# Uni-2_0_Complete.net
KiCad netlist of a schematic drawn in EAGLE
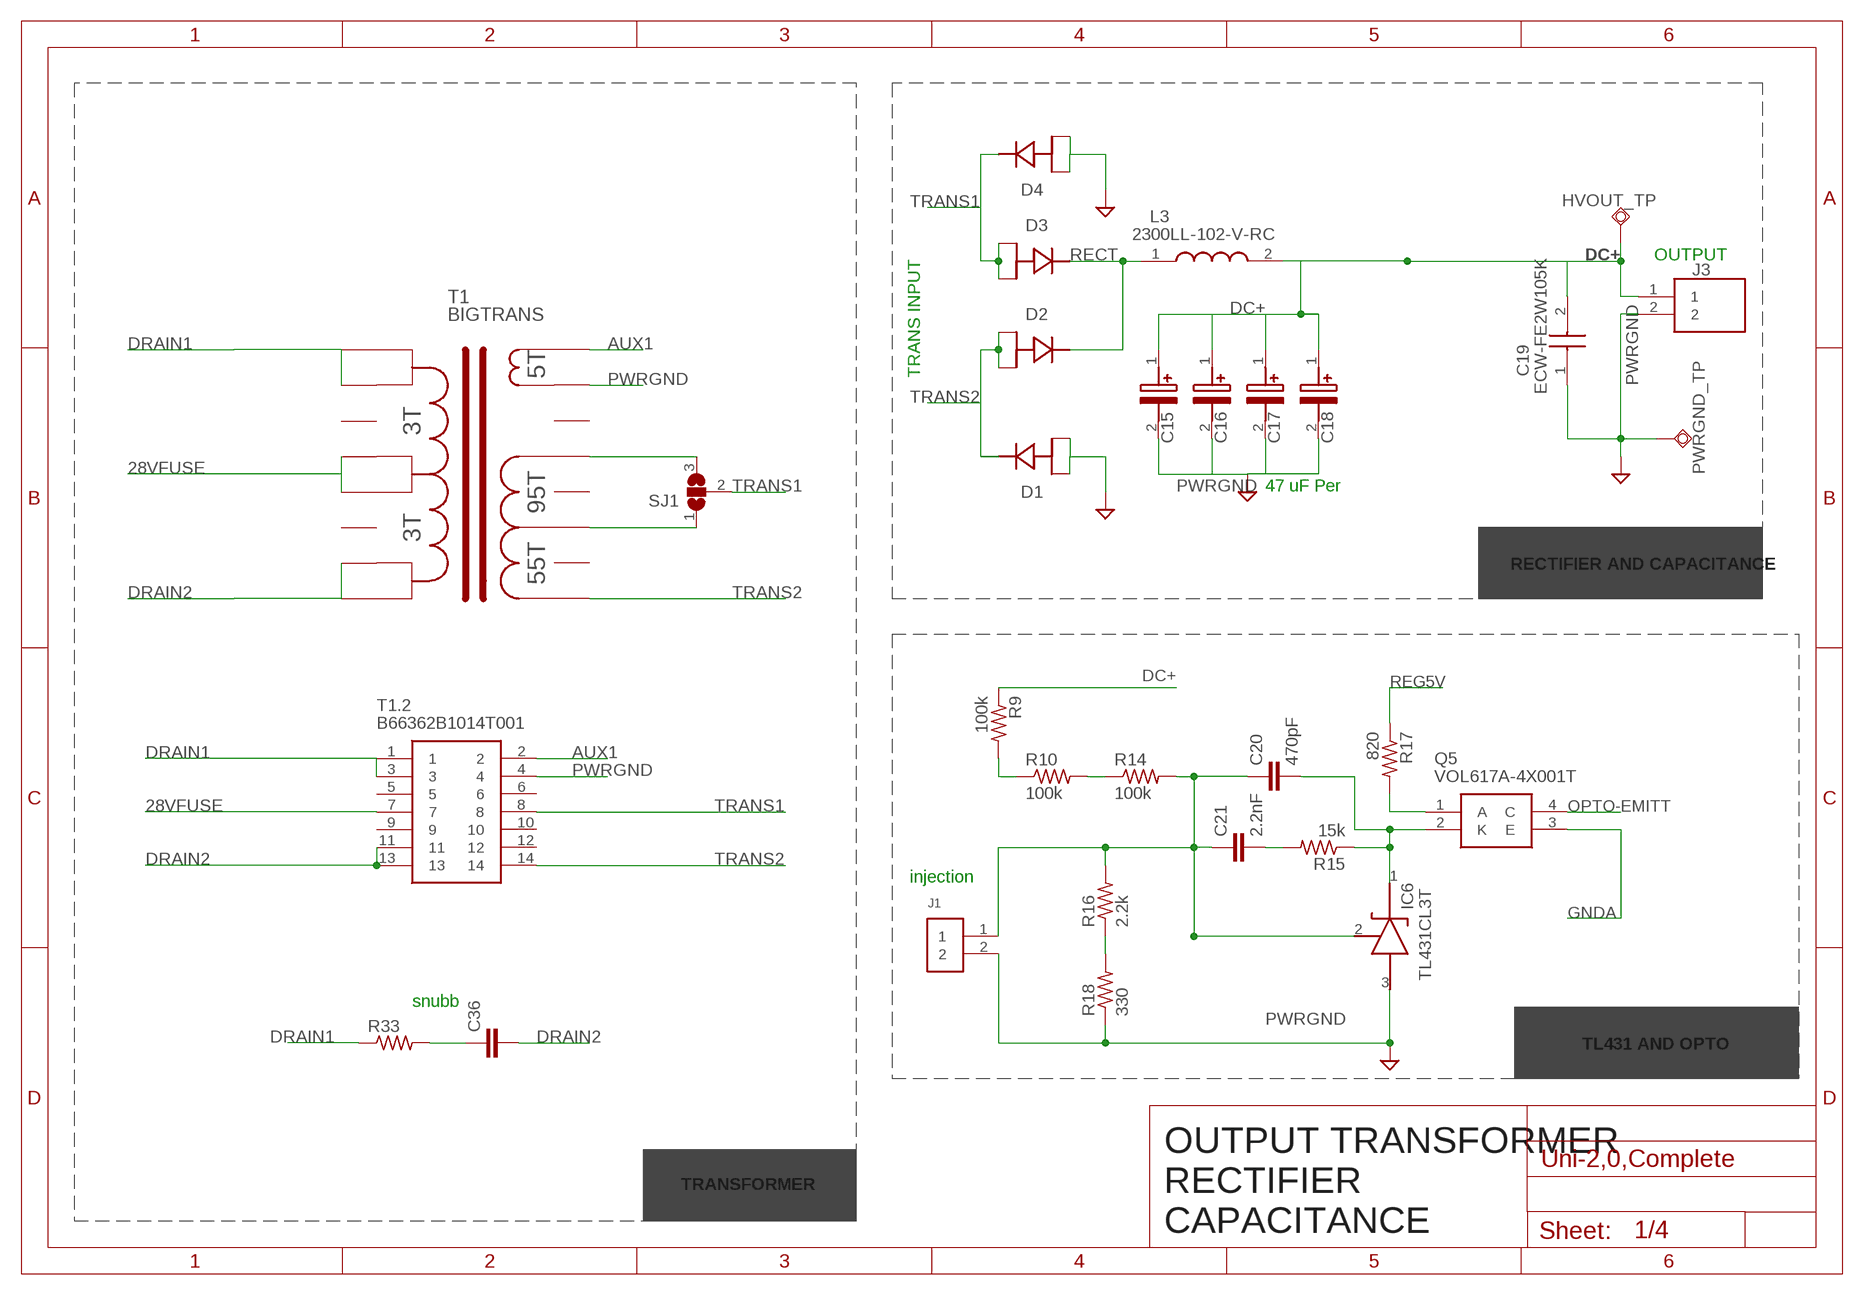
[diagram p0: schematic, sheet 1]
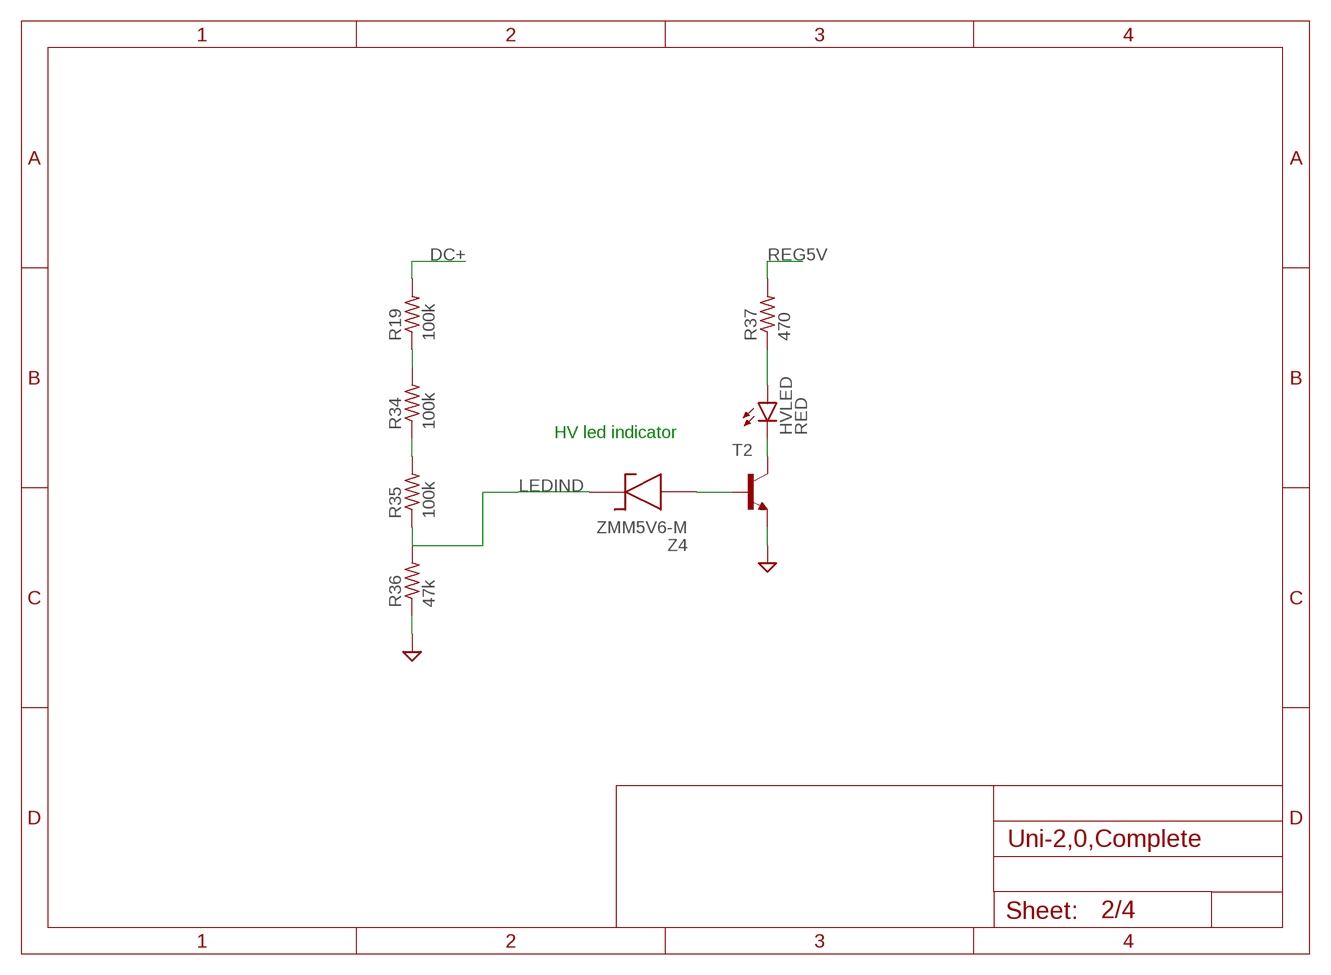
[diagram p1: schematic, sheet 2]
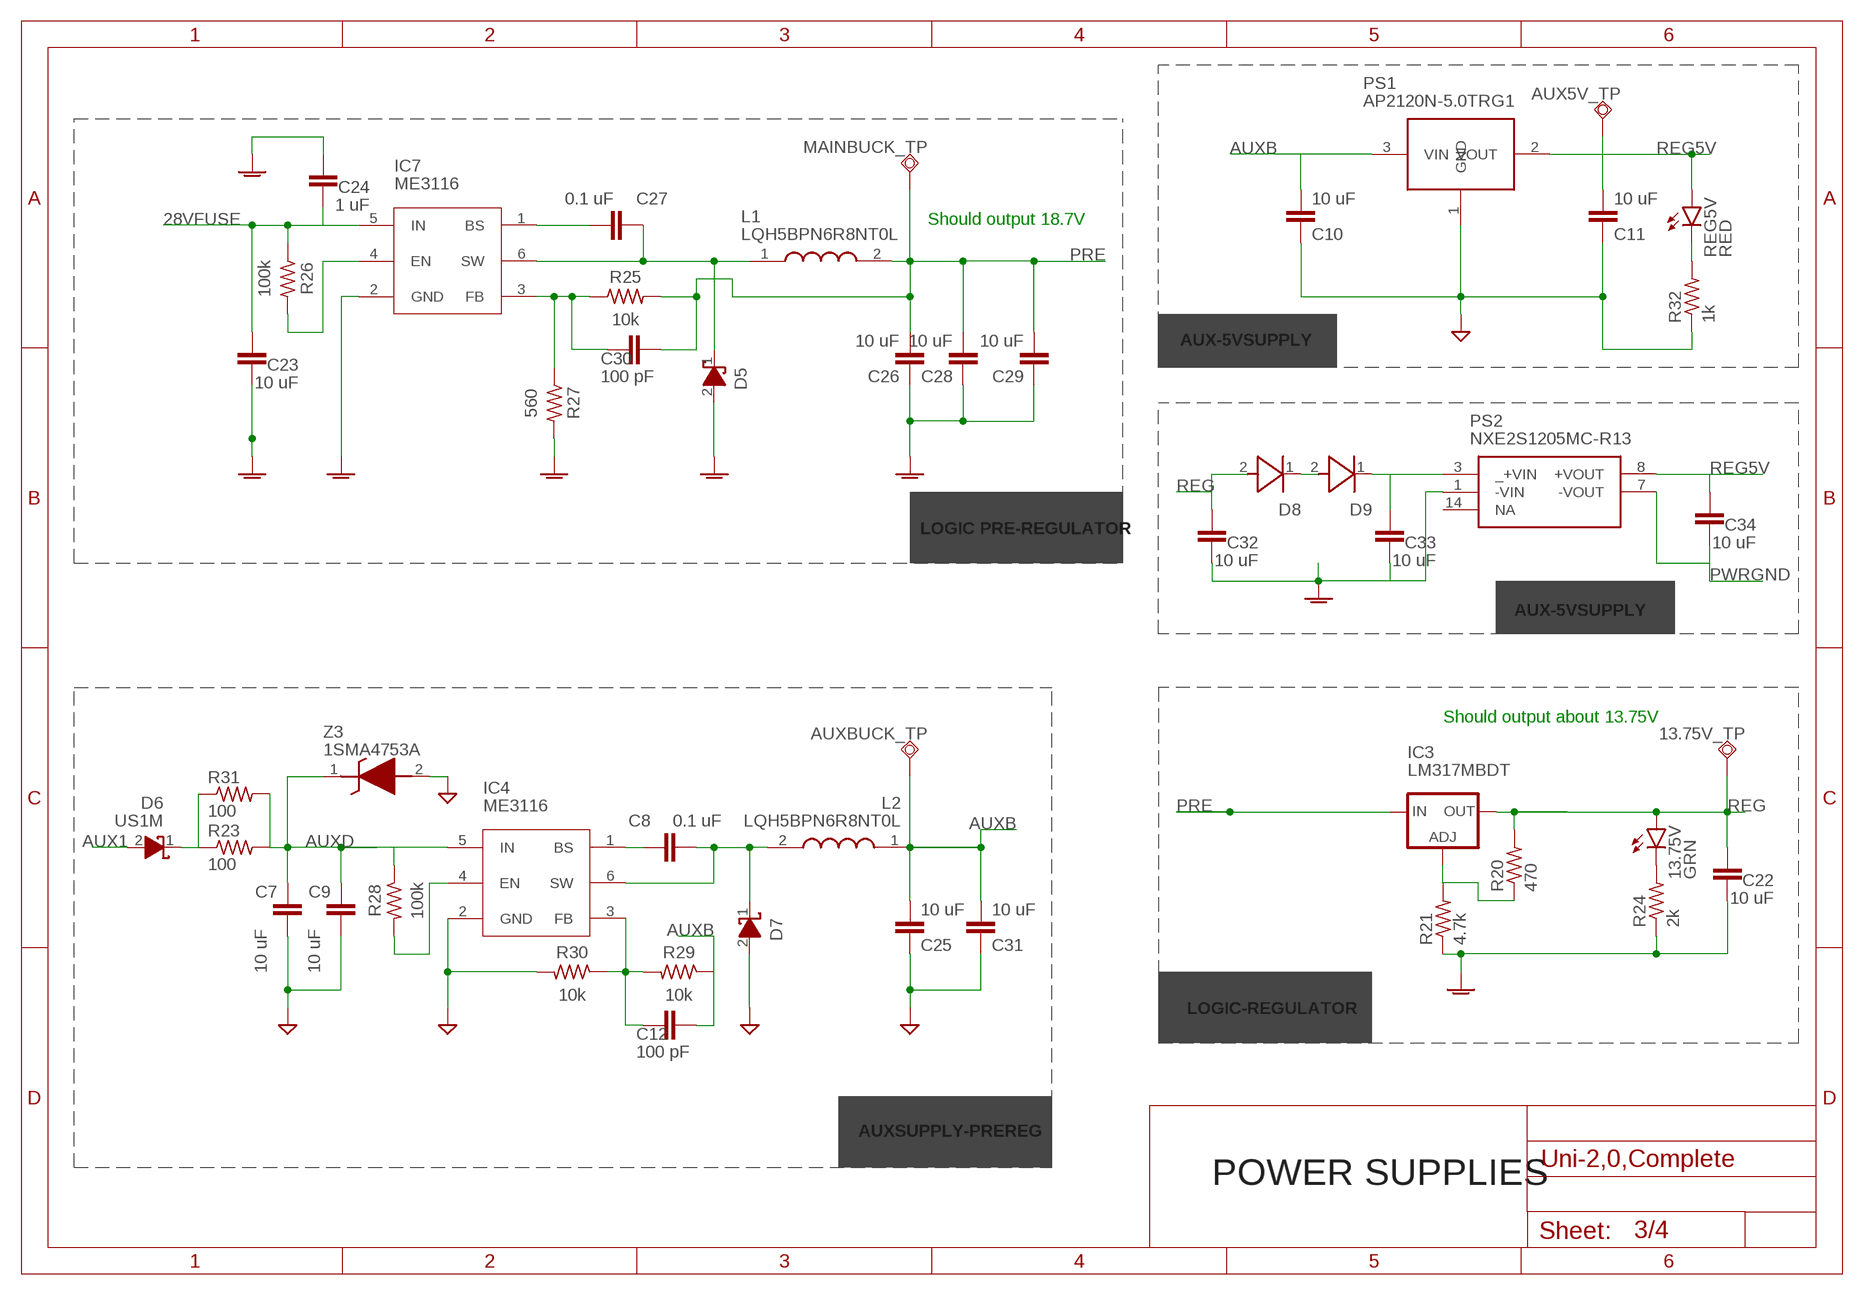
[diagram p2: schematic, sheet 3]
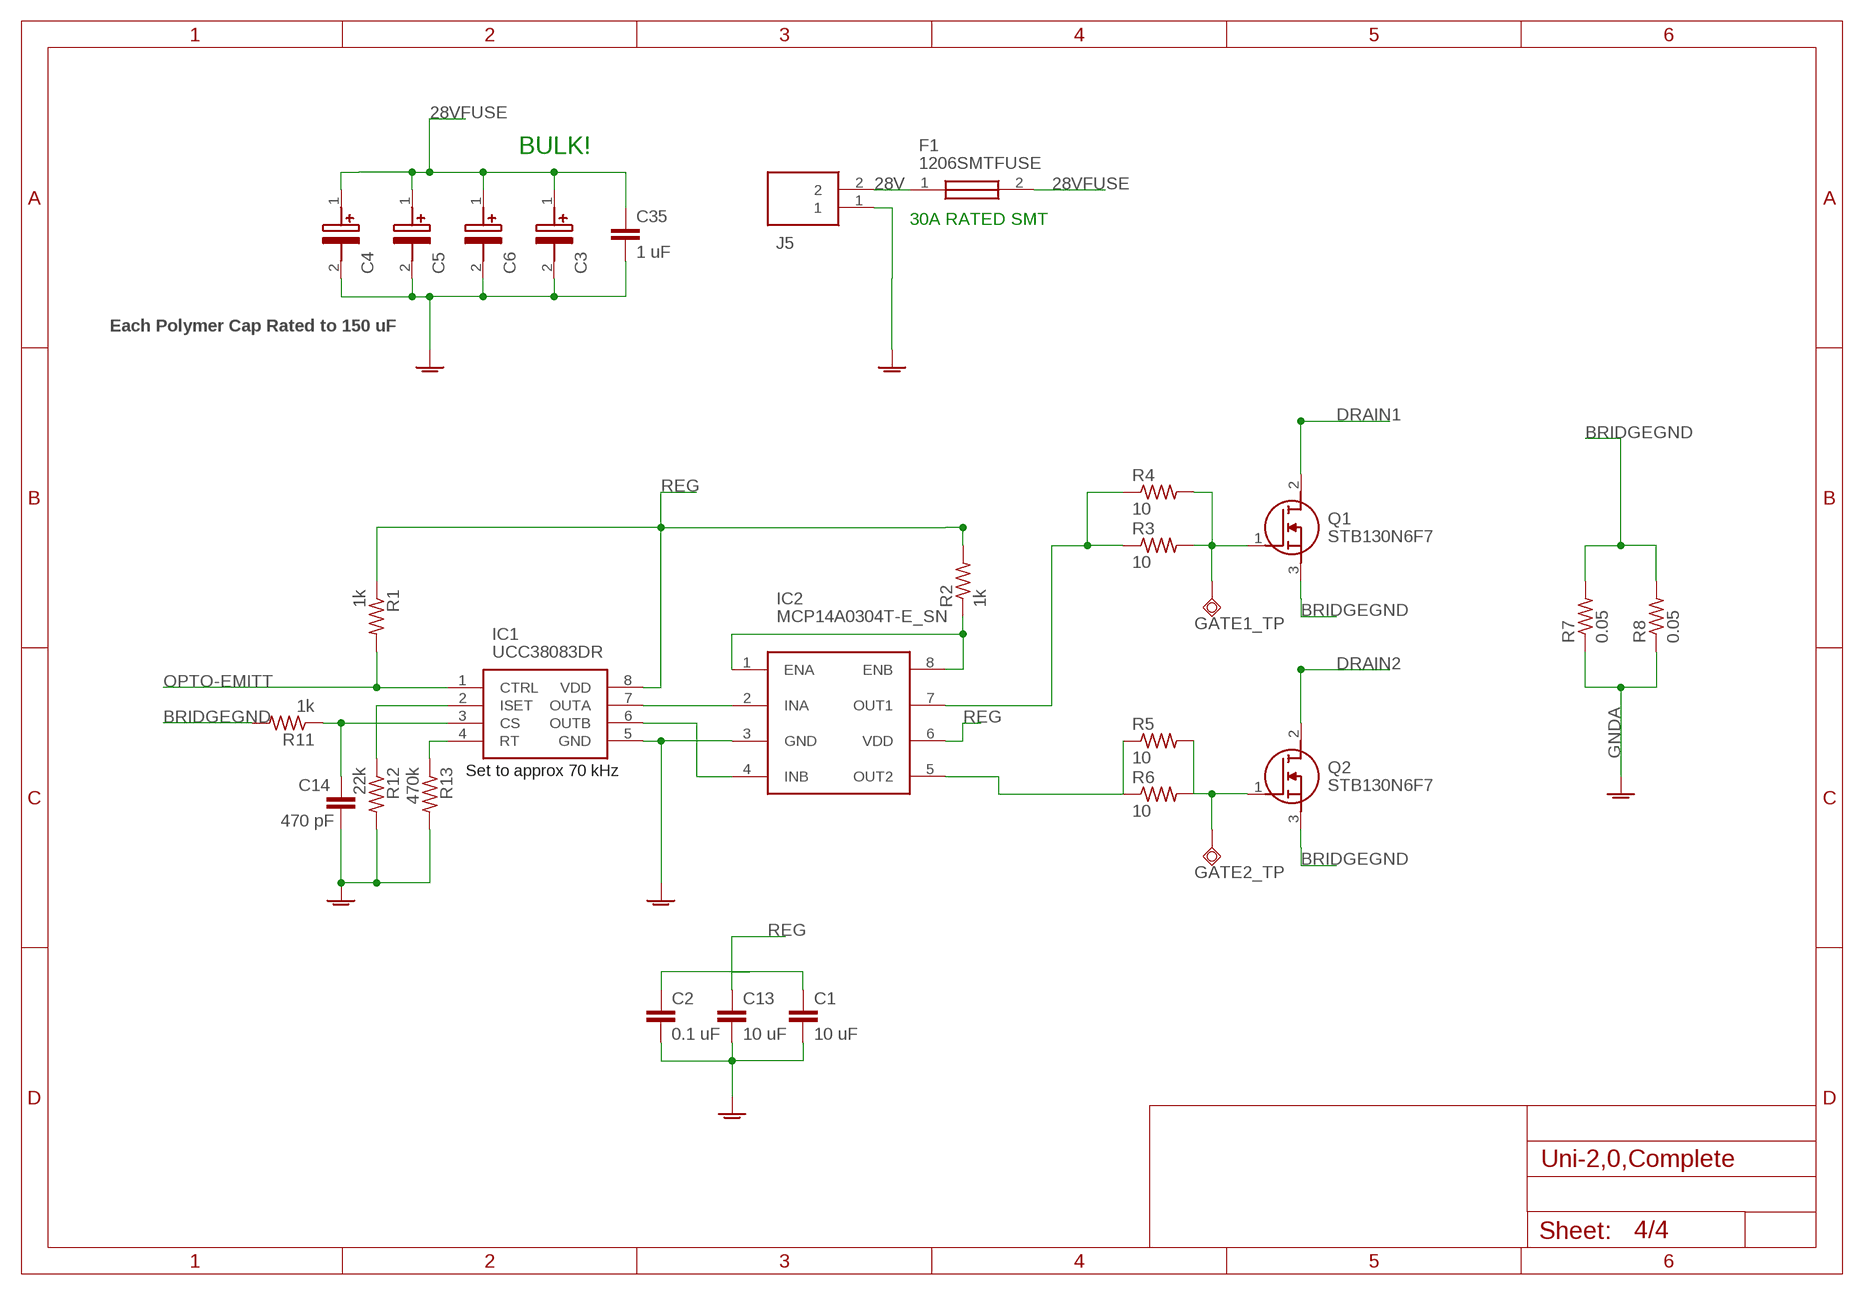
[diagram p3: schematic, sheet 4]

(export (version "E")
  (design (tool "Eeschema 10.0.6"))
  (components
    (comp (ref "C15")
      (value "EEU-ED2V470S")
      (footprint "eagle-import:CAPPRD750W85D1800H2200")
      (fields (field (name "MOUSER_PART_NUMBER") "667-EEU-ED2V470S"))
      (libsource (lib "eagle-import") (part "EEU-ED2V470S"))
    )
    (comp (ref "C16")
      (value "EEU-ED2V470S")
      (footprint "eagle-import:CAPPRD750W85D1800H2200")
      (fields (field (name "MOUSER_PART_NUMBER") "667-EEU-ED2V470S"))
      (libsource (lib "eagle-import") (part "EEU-ED2V470S"))
    )
    (comp (ref "C17")
      (value "EEU-ED2V470S")
      (footprint "eagle-import:CAPPRD750W85D1800H2200")
      (fields (field (name "MOUSER_PART_NUMBER") "667-EEU-ED2V470S"))
      (libsource (lib "eagle-import") (part "EEU-ED2V470S"))
    )
    (comp (ref "C18")
      (value "EEU-ED2V470S")
      (footprint "eagle-import:CAPPRD750W85D1800H2200")
      (fields (field (name "MOUSER_PART_NUMBER") "667-EEU-ED2V470S"))
      (libsource (lib "eagle-import") (part "EEU-ED2V470S"))
    )
    (comp (ref "C19")
      (value "ECW-FE2W105K")
      (footprint "eagle-import:ECWFE2W105K")
      (libsource (lib "eagle-import") (part "ECW-FE2W105K"))
    )
    (comp (ref "C20")
      (value "470pF")
      (footprint "eagle-import:C0603K")
      (libsource (lib "eagle-import") (part "rcl_334_C-EUC0603K"))
    )
    (comp (ref "C21")
      (value "2.2nF")
      (footprint "eagle-import:C0603K")
      (libsource (lib "eagle-import") (part "rcl_334_C-EUC0603K"))
    )
    (comp (ref "C36")
      (value "C-EUC1210K")
      (footprint "eagle-import:C1210K")
      (libsource (lib "eagle-import") (part "rcl_334_C-EUC1210K"))
    )
    (comp (ref "D1")
      (value "FERD20H60CG-TR")
      (footprint "eagle-import:STB20N95K5")
      (fields (field (name "MOUSER_PART_NUMBER") "511-FERD20H60CG-TR"))
      (libsource (lib "eagle-import") (part "FERD20H60CG-TR"))
    )
    (comp (ref "D2")
      (value "FERD20H60CG-TR")
      (footprint "eagle-import:STB20N95K5")
      (fields (field (name "MOUSER_PART_NUMBER") "511-FERD20H60CG-TR"))
      (libsource (lib "eagle-import") (part "FERD20H60CG-TR"))
    )
    (comp (ref "D3")
      (value "FERD20H60CG-TR")
      (footprint "eagle-import:STB20N95K5")
      (fields (field (name "MOUSER_PART_NUMBER") "511-FERD20H60CG-TR"))
      (libsource (lib "eagle-import") (part "FERD20H60CG-TR"))
    )
    (comp (ref "D4")
      (value "FERD20H60CG-TR")
      (footprint "eagle-import:STB20N95K5")
      (fields (field (name "MOUSER_PART_NUMBER") "511-FERD20H60CG-TR"))
      (libsource (lib "eagle-import") (part "FERD20H60CG-TR"))
    )
    (comp (ref "HVOUT_TP")
      (value "TPSQPAD1-13")
      (footprint "eagle-import:P1-13")
      (libsource (lib "eagle-import") (part "TPSQPAD1-13"))
    )
    (comp (ref "IC6")
      (value "TL431CL3T")
      (footprint "eagle-import:SOT95P237X112-3N")
      (fields (field (name "MOUSER_PART_NUMBER") "511-TL431CL3T"))
      (libsource (lib "eagle-import") (part "TL431CL3T"))
    )
    (comp (ref "J1")
      (value "61300211121")
      (footprint "eagle-import:61300211121")
      (fields
        (field (name "DIGI_KEY_PART_NUMBER") "732-5315-ND")
        (field (name "MANUFACTURER") "Wurth Electronics Inc.")
        (field (name "CREATED_BY") "PCBLayout.com")
      )
      (libsource (lib "eagle-import") (part "61300211121"))
    )
    (comp (ref "J3")
      (value "2305908-2")
      (footprint "eagle-import:23059082")
      (fields (field (name "MOUSER_PART_NUMBER") "571-2305908-2"))
      (libsource (lib "eagle-import") (part "2305908-2"))
    )
    (comp (ref "L3")
      (value "2300LL-102-V-RC")
      (footprint "eagle-import:2300LL102VRC")
      (fields (field (name "MOUSER_PART_NUMBER") "652-2300LL-102-V-RC"))
      (libsource (lib "eagle-import") (part "2300LL-102-V-RC"))
    )
    (comp (ref "PWRGND_TP")
      (value "TPSQPAD1-13")
      (footprint "eagle-import:P1-13")
      (libsource (lib "eagle-import") (part "TPSQPAD1-13"))
    )
    (comp (ref "Q5")
      (value "VOL617A-4X001T")
      (footprint "eagle-import:SOP254P1015X230-4N")
      (fields (field (name "MOUSER_PART_NUMBER") "78-VOL617A-4X001T"))
      (libsource (lib "eagle-import") (part "VOL617A-4X001T"))
    )
    (comp (ref "R9")
      (value "100k")
      (footprint "eagle-import:R1206")
      (libsource (lib "eagle-import") (part "R-US_R1206"))
    )
    (comp (ref "R10")
      (value "100k")
      (footprint "eagle-import:R1206")
      (libsource (lib "eagle-import") (part "R-US_R1206"))
    )
    (comp (ref "R14")
      (value "100k")
      (footprint "eagle-import:R1206")
      (libsource (lib "eagle-import") (part "R-US_R1206"))
    )
    (comp (ref "R15")
      (value "15k")
      (footprint "eagle-import:R0603")
      (libsource (lib "eagle-import") (part "R-US_R0603"))
    )
    (comp (ref "R16")
      (value "2.2k")
      (footprint "eagle-import:R0805")
      (libsource (lib "eagle-import") (part "R-US_R0805"))
    )
    (comp (ref "R17")
      (value "820")
      (footprint "eagle-import:R0603")
      (libsource (lib "eagle-import") (part "R-US_R0603"))
    )
    (comp (ref "R18")
      (value "330")
      (footprint "eagle-import:R0805")
      (libsource (lib "eagle-import") (part "R-US_R0805"))
    )
    (comp (ref "R33")
      (value "R-US_R1206")
      (footprint "eagle-import:R1206")
      (libsource (lib "eagle-import") (part "R-US_R1206"))
    )
    (comp (ref "SJ1")
      (value "SJ2WW")
      (footprint "eagle-import:SJ_2W")
      (libsource (lib "eagle-import") (part "SJ2WW"))
    )
    (comp (ref "T1")
      (value "BIGTRANS")
      (footprint "eagle-import:BIGTRANS!")
      (libsource (lib "eagle-import") (part "BIGTRANS"))
    )
    (comp (ref "T1.2")
      (value "B66362B1014T001")
      (footprint "eagle-import:B66362B1014T001")
      (fields (field (name "MOUSER_PART_NUMBER") "871-B66362B1014T001"))
      (libsource (lib "eagle-import") (part "B66362B1014T001"))
    )
    (comp (ref "C1")
      (value "10 uF")
      (footprint "eagle-import:C0603K")
      (fields (field (name "LCSC_PART") "C440198"))
      (libsource (lib "eagle-import") (part "rcl_334_C-EUC0603K"))
    )
    (comp (ref "C2")
      (value "0.1 uF")
      (footprint "eagle-import:C0603K")
      (fields (field (name "LCSC_PART") "C440198"))
      (libsource (lib "eagle-import") (part "rcl_334_C-EUC0603K"))
    )
    (comp (ref "C3")
      (value "OVK151M1VTR-10131")
      (footprint "eagle-import:16SVF1000M")
      (libsource (lib "eagle-import") (part "OVK151M1VTR-10131"))
    )
    (comp (ref "C4")
      (value "OVK151M1VTR-10131")
      (footprint "eagle-import:16SVF1000M")
      (libsource (lib "eagle-import") (part "OVK151M1VTR-10131"))
    )
    (comp (ref "C5")
      (value "OVK151M1VTR-10131")
      (footprint "eagle-import:16SVF1000M")
      (libsource (lib "eagle-import") (part "OVK151M1VTR-10131"))
    )
    (comp (ref "C6")
      (value "OVK151M1VTR-10131")
      (footprint "eagle-import:16SVF1000M")
      (libsource (lib "eagle-import") (part "OVK151M1VTR-10131"))
    )
    (comp (ref "C13")
      (value "10 uF")
      (footprint "eagle-import:C0603K")
      (fields (field (name "LCSC_PART") "C440198"))
      (libsource (lib "eagle-import") (part "rcl_334_C-EUC0603K"))
    )
    (comp (ref "C14")
      (value "470 pF")
      (footprint "eagle-import:C0603K")
      (fields (field (name "LCSC_PART") "C1620"))
      (libsource (lib "eagle-import") (part "rcl_334_C-EUC0603K"))
    )
    (comp (ref "C35")
      (value "1 uF")
      (footprint "eagle-import:C0805K")
      (fields (field (name "LCSC_PART") "C440198"))
      (libsource (lib "eagle-import") (part "rcl_334_C-EUC0805K"))
    )
    (comp (ref "F1")
      (value "1206SMTFUSE")
      (footprint "eagle-import:1206SMTFUSE")
      (fields
        (field (name "MANUFACTURER_PART_NUMBER") "0685P9400-01")
        (field (name "MOUSER_PART_NUMBER") "530-0685P9400-01")
      )
      (libsource (lib "eagle-import") (part "1206SMTFUSE"))
    )
    (comp (ref "GATE1_TP")
      (value "TPSQPAD1-17")
      (footprint "eagle-import:P1-17")
      (libsource (lib "eagle-import") (part "TPSQPAD1-17"))
    )
    (comp (ref "GATE2_TP")
      (value "TPSQPAD1-17")
      (footprint "eagle-import:P1-17")
      (libsource (lib "eagle-import") (part "TPSQPAD1-17"))
    )
    (comp (ref "IC1")
      (value "UCC38083DR")
      (footprint "eagle-import:SOIC127P600X175-8N")
      (fields (field (name "MOUSER_PART_NUMBER") "595-UCC38083DR"))
      (libsource (lib "eagle-import") (part "UCC38083DR"))
    )
    (comp (ref "IC2")
      (value "MCP14A0304T-E_SN")
      (footprint "eagle-import:SOIC127P600X175-8N")
      (fields
        (field (name "MANUFACTURER_PART_NUMBER") "MCP14A0304T-E/SN")
        (field (name "MOUSER_PART_NUMBER") "579-MCP14A0304T-E/SN")
      )
      (libsource (lib "eagle-import") (part "MCP14A0304T-E_SN"))
    )
    (comp (ref "J5")
      (value "2305908-2")
      (footprint "eagle-import:23059082")
      (fields (field (name "MOUSER_PART_NUMBER") "571-2305908-2"))
      (libsource (lib "eagle-import") (part "2305908-2"))
    )
    (comp (ref "Q1")
      (value "STB130N6F7")
      (footprint "eagle-import:D2PAK")
      (libsource (lib "eagle-import") (part "STB130N6F7"))
    )
    (comp (ref "Q2")
      (value "STB130N6F7")
      (footprint "eagle-import:D2PAK")
      (libsource (lib "eagle-import") (part "STB130N6F7"))
    )
    (comp (ref "R1")
      (value "1k")
      (footprint "eagle-import:R0603")
      (fields (field (name "LCSC_PART") "C22975"))
      (libsource (lib "eagle-import") (part "R-US_R0603"))
    )
    (comp (ref "R2")
      (value "1k")
      (footprint "eagle-import:R0402")
      (libsource (lib "eagle-import") (part "R-US_R0402"))
    )
    (comp (ref "R3")
      (value "10")
      (footprint "eagle-import:R0805")
      (libsource (lib "eagle-import") (part "R-US_R0805"))
    )
    (comp (ref "R4")
      (value "10")
      (footprint "eagle-import:R0805")
      (libsource (lib "eagle-import") (part "R-US_R0805"))
    )
    (comp (ref "R5")
      (value "10")
      (footprint "eagle-import:R0805")
      (libsource (lib "eagle-import") (part "R-US_R0805"))
    )
    (comp (ref "R6")
      (value "10")
      (footprint "eagle-import:R0805")
      (libsource (lib "eagle-import") (part "R-US_R0805"))
    )
    (comp (ref "R7")
      (value "0.05")
      (footprint "eagle-import:R2512")
      (libsource (lib "eagle-import") (part "R-US_R2512"))
    )
    (comp (ref "R8")
      (value "0.05")
      (footprint "eagle-import:R2512")
      (libsource (lib "eagle-import") (part "R-US_R2512"))
    )
    (comp (ref "R11")
      (value "1k")
      (footprint "eagle-import:R0603")
      (fields (field (name "LCSC_PART") "C21190"))
      (libsource (lib "eagle-import") (part "R-US_R0603"))
    )
    (comp (ref "R12")
      (value "22k")
      (footprint "eagle-import:R0603")
      (fields (field (name "LCSC_PART") "C31850"))
      (libsource (lib "eagle-import") (part "R-US_R0603"))
    )
    (comp (ref "R13")
      (value "470k")
      (footprint "eagle-import:R0603")
      (fields (field (name "LCSC_PART") "C25811"))
      (libsource (lib "eagle-import") (part "R-US_R0603"))
    )
    (comp (ref "HVLED")
      (value "RED")
      (footprint "eagle-import:CHIPLED_0805")
      (libsource (lib "eagle-import") (part "LEDCHIPLED_0805"))
    )
    (comp (ref "R19")
      (value "100k")
      (footprint "eagle-import:R1206")
      (libsource (lib "eagle-import") (part "R-US_R1206"))
    )
    (comp (ref "R34")
      (value "100k")
      (footprint "eagle-import:R1206")
      (libsource (lib "eagle-import") (part "R-US_R1206"))
    )
    (comp (ref "R35")
      (value "100k")
      (footprint "eagle-import:R1206")
      (libsource (lib "eagle-import") (part "R-US_R1206"))
    )
    (comp (ref "R36")
      (value "47k")
      (footprint "eagle-import:R0805")
      (libsource (lib "eagle-import") (part "R-US_R0805"))
    )
    (comp (ref "R37")
      (value "470")
      (footprint "eagle-import:R0603")
      (libsource (lib "eagle-import") (part "R-US_R0603"))
    )
    (comp (ref "T2")
      (value "MMBT3904LT1-NPN-SOT23-BEC")
      (footprint "eagle-import:SOT23-BEC")
      (libsource (lib "eagle-import") (part "-NPN-SOT23-BECMMBT3904LT1"))
    )
    (comp (ref "Z4")
      (value "ZMM5V6-M")
      (footprint "eagle-import:BZV55C5V6L1")
      (fields
        (field (name "MANUFACTURER_PART_NUMBER") "BZV55C5V6 L1")
        (field (name "MOUSER_PART_NUMBER") "821-BZV55C5V6L1")
      )
      (libsource (lib "eagle-import") (part "BZV55C5V6_L1"))
    )
    (comp (ref "13.75V")
      (value "GRN")
      (footprint "eagle-import:CHIPLED_0805")
      (fields (field (name "LCSC_PART") "C72043"))
      (libsource (lib "eagle-import") (part "LEDCHIPLED_0805"))
    )
    (comp (ref "13.75V_TP")
      (value "TPSQPAD1-17")
      (footprint "eagle-import:P1-17")
      (libsource (lib "eagle-import") (part "TPSQPAD1-17"))
    )
    (comp (ref "AUX5V_TP")
      (value "TPSQPAD1-17")
      (footprint "eagle-import:P1-17")
      (libsource (lib "eagle-import") (part "TPSQPAD1-17"))
    )
    (comp (ref "AUXBUCK_TP")
      (value "TPSQPAD1-17")
      (footprint "eagle-import:P1-17")
      (libsource (lib "eagle-import") (part "TPSQPAD1-17"))
    )
    (comp (ref "C7")
      (value "10 uF")
      (footprint "eagle-import:C0805K")
      (libsource (lib "eagle-import") (part "rcl_334_C-EUC0805K"))
    )
    (comp (ref "C8")
      (value "0.1 uF")
      (footprint "eagle-import:C0603K")
      (fields (field (name "LCSC_PART") "C14663"))
      (libsource (lib "eagle-import") (part "rcl_334_C-EUC0603K"))
    )
    (comp (ref "C9")
      (value "10 uF")
      (footprint "eagle-import:C0805K")
      (libsource (lib "eagle-import") (part "rcl_334_C-EUC0805K"))
    )
    (comp (ref "C10")
      (value "10 uF")
      (footprint "eagle-import:C0603K")
      (fields (field (name "LCSC_PART") "C440198"))
      (libsource (lib "eagle-import") (part "rcl_334_C-EUC0603K"))
    )
    (comp (ref "C11")
      (value "10 uF")
      (footprint "eagle-import:C0603K")
      (libsource (lib "eagle-import") (part "rcl_334_C-EUC0603K"))
    )
    (comp (ref "C12")
      (value "100 pF")
      (footprint "eagle-import:C0402K")
      (fields (field (name "LCSC_PART") "C1546"))
      (libsource (lib "eagle-import") (part "rcl_334_C-EUC0402K"))
    )
    (comp (ref "C22")
      (value "10 uF")
      (footprint "eagle-import:C0805K")
      (fields (field (name "LCSC_PART") "C440198"))
      (libsource (lib "eagle-import") (part "C-EUC0805K"))
    )
    (comp (ref "C23")
      (value "10 uF")
      (footprint "eagle-import:C0805K")
      (fields (field (name "LCSC_PART") "C440198"))
      (libsource (lib "eagle-import") (part "C-EUC0805K"))
    )
    (comp (ref "C24")
      (value "1 uF")
      (footprint "eagle-import:C0603K")
      (fields (field (name "LCSC_PART") "C440198"))
      (libsource (lib "eagle-import") (part "rcl_334_C-EUC0603K"))
    )
    (comp (ref "C25")
      (value "10 uF")
      (footprint "eagle-import:C0603K")
      (fields (field (name "LCSC_PART") "C440198"))
      (libsource (lib "eagle-import") (part "rcl_334_C-EUC0603K"))
    )
    (comp (ref "C26")
      (value "10 uF")
      (footprint "eagle-import:C0805K")
      (fields (field (name "LCSC_PART") "C440198"))
      (libsource (lib "eagle-import") (part "C-EUC0805K"))
    )
    (comp (ref "C27")
      (value "0.1 uF")
      (footprint "eagle-import:C0603K")
      (fields (field (name "LCSC_PART") "C14663"))
      (libsource (lib "eagle-import") (part "rcl_334_C-EUC0603K"))
    )
    (comp (ref "C28")
      (value "10 uF")
      (footprint "eagle-import:C0805K")
      (fields (field (name "LCSC_PART") "C440198"))
      (libsource (lib "eagle-import") (part "C-EUC0805K"))
    )
    (comp (ref "C29")
      (value "10 uF")
      (footprint "eagle-import:C0805K")
      (fields (field (name "LCSC_PART") "C440198"))
      (libsource (lib "eagle-import") (part "C-EUC0805K"))
    )
    (comp (ref "C30")
      (value "100 pF")
      (footprint "eagle-import:C0402K")
      (fields (field (name "LCSC_PART") "C1546"))
      (libsource (lib "eagle-import") (part "rcl_334_C-EUC0402K"))
    )
    (comp (ref "C31")
      (value "10 uF")
      (footprint "eagle-import:C0402")
      (fields (field (name "LCSC_PART") "C440198"))
      (libsource (lib "eagle-import") (part "rcl_334_C-EUC0402"))
    )
    (comp (ref "C32")
      (value "10 uF")
      (footprint "eagle-import:C0805K")
      (fields (field (name "LCSC_PART") "C440198"))
      (libsource (lib "eagle-import") (part "C-EUC0805K"))
    )
    (comp (ref "C33")
      (value "10 uF")
      (footprint "eagle-import:C0603K")
      (fields (field (name "LCSC_PART") "C440198"))
      (libsource (lib "eagle-import") (part "rcl_334_C-EUC0603K"))
    )
    (comp (ref "C34")
      (value "10 uF")
      (footprint "eagle-import:C0603K")
      (fields (field (name "LCSC_PART") "C440198"))
      (libsource (lib "eagle-import") (part "rcl_334_C-EUC0603K"))
    )
    (comp (ref "D5")
      (value "SCHOTTKY")
      (footprint "eagle-import:DIOM5127X229N")
      (fields
        (field (name "MANUFACTURER_PART_NUMBER") "SS16HE3_B/H")
        (field (name "MOUSER_PART_NUMBER") "78-SS16HE3_B/H")
        (field (name "LCSC_PART") "C22452")
      )
      (libsource (lib "eagle-import") (part "SCHOTTKY"))
    )
    (comp (ref "D6")
      (value "US1M")
      (footprint "eagle-import:DIOM5127X229N")
      (fields
        (field (name "MANUFACTURER_PART_NUMBER") "SS16HE3_B/H")
        (field (name "MOUSER_PART_NUMBER") "78-SS16HE3_B/H")
      )
      (libsource (lib "eagle-import") (part "SCHOTTKY"))
    )
    (comp (ref "D7")
      (value "SCHOTTKY")
      (footprint "eagle-import:DIOM5127X229N")
      (fields
        (field (name "MANUFACTURER_PART_NUMBER") "SS16HE3_B/H")
        (field (name "MOUSER_PART_NUMBER") "78-SS16HE3_B/H")
        (field (name "LCSC_PART") "C22452")
      )
      (libsource (lib "eagle-import") (part "SCHOTTKY"))
    )
    (comp (ref "D8")
      (value "SM4007PL")
      (footprint "eagle-import:SOD3716X145N")
      (fields
        (field (name "MANUFACTURER_PART_NUMBER") "1N4148W-7-F")
        (field (name "MOUSER_PART_NUMBER") "621-1N4148W-F")
        (field (name "LCSC_PART") "C64898")
      )
      (libsource (lib "eagle-import") (part "1N4148W-7-F"))
    )
    (comp (ref "D9")
      (value "SM4007PL")
      (footprint "eagle-import:SOD3716X145N")
      (fields
        (field (name "MANUFACTURER_PART_NUMBER") "1N4148W-7-F")
        (field (name "MOUSER_PART_NUMBER") "621-1N4148W-F")
        (field (name "LCSC_PART") "C64898")
      )
      (libsource (lib "eagle-import") (part "1N4148W-7-F"))
    )
    (comp (ref "IC3")
      (value "LM317MBDT")
      (footprint "eagle-import:DPACK")
      (libsource (lib "eagle-import") (part "LM317?MBDT"))
    )
    (comp (ref "IC4")
      (value "ME3116")
      (footprint "eagle-import:SOT95P280X100-6N")
      (fields (field (name "LCSC_PART") "C97643"))
      (libsource (lib "eagle-import") (part "ME3116"))
    )
    (comp (ref "IC7")
      (value "ME3116")
      (footprint "eagle-import:SOT95P280X100-6N")
      (fields (field (name "LCSC_PART") "C97643"))
      (libsource (lib "eagle-import") (part "ME3116"))
    )
    (comp (ref "L1")
      (value "LQH5BPN6R8NT0L")
      (footprint "eagle-import:LQH5BPB100MT0L")
      (fields (field (name "MOUSER_PART_NUMBER") "81-LQH5BPN6R8NT0L0L"))
      (libsource (lib "eagle-import") (part "LQH5BPN6R8NT0L"))
    )
    (comp (ref "L2")
      (value "LQH5BPN6R8NT0L")
      (footprint "eagle-import:LQH5BPB100MT0L")
      (fields (field (name "MOUSER_PART_NUMBER") "81-LQH5BPN6R8NT0L0L"))
      (libsource (lib "eagle-import") (part "LQH5BPN6R8NT0L"))
    )
    (comp (ref "MAINBUCK_TP")
      (value "TPSQPAD1-17")
      (footprint "eagle-import:P1-17")
      (libsource (lib "eagle-import") (part "TPSQPAD1-17"))
    )
    (comp (ref "PS1")
      (value "AP2120N-5.0TRG1")
      (footprint "eagle-import:SOT95P240X120-3N")
      (fields (field (name "MOUSER_PART_NUMBER") "621-AP2120N-5.0TRG1"))
      (libsource (lib "eagle-import") (part "AP2120N-5.0TRG1"))
    )
    (comp (ref "PS2")
      (value "NXE2S1205MC-R13")
      (footprint "eagle-import:NXE2S1205MCR13")
      (fields (field (name "MOUSER_PART_NUMBER") "580-NXE2S1205MC-R13"))
      (libsource (lib "eagle-import") (part "NXE2S1205MC-R13"))
    )
    (comp (ref "R20")
      (value "470")
      (footprint "eagle-import:R0603")
      (fields (field (name "LCSC_PART") "C22975"))
      (libsource (lib "eagle-import") (part "R-US_R0603"))
    )
    (comp (ref "R21")
      (value "4.7k")
      (footprint "eagle-import:R0603")
      (fields (field (name "LCSC_PART") "C22975"))
      (libsource (lib "eagle-import") (part "R-US_R0603"))
    )
    (comp (ref "R23")
      (value "100")
      (footprint "eagle-import:R1206")
      (libsource (lib "eagle-import") (part "R-US_R1206"))
    )
    (comp (ref "R24")
      (value "2k")
      (footprint "eagle-import:R0603")
      (fields (field (name "LCSC_PART") "C22975"))
      (libsource (lib "eagle-import") (part "R-US_R0603"))
    )
    (comp (ref "R25")
      (value "10k")
      (footprint "eagle-import:R0402")
      (fields (field (name "LCSC_PART") "C25779"))
      (libsource (lib "eagle-import") (part "R-US_R0402"))
    )
    (comp (ref "R26")
      (value "100k")
      (footprint "eagle-import:R0402")
      (fields (field (name "LCSC_PART") "C25741") (field (name "SPICEPREFIX") "R"))
      (libsource (lib "eagle-import") (part "R-US_R0402"))
    )
    (comp (ref "R27")
      (value "560")
      (footprint "eagle-import:R0402")
      (fields (field (name "LCSC_PART") "C4177") (field (name "SPICEPREFIX") "R"))
      (libsource (lib "eagle-import") (part "R-US_R0402"))
    )
    (comp (ref "R28")
      (value "100k")
      (footprint "eagle-import:R0402")
      (fields (field (name "LCSC_PART") "C25741") (field (name "SPICEPREFIX") "R"))
      (libsource (lib "eagle-import") (part "R-US_R0402"))
    )
    (comp (ref "R29")
      (value "10k")
      (footprint "eagle-import:R0402")
      (fields (field (name "LCSC_PART") "C25779"))
      (libsource (lib "eagle-import") (part "R-US_R0402"))
    )
    (comp (ref "R30")
      (value "10k")
      (footprint "eagle-import:R0402")
      (fields (field (name "LCSC_PART") "C25779"))
      (libsource (lib "eagle-import") (part "R-US_R0402"))
    )
    (comp (ref "R31")
      (value "100")
      (footprint "eagle-import:R1206")
      (libsource (lib "eagle-import") (part "R-US_R1206"))
    )
    (comp (ref "R32")
      (value "1k")
      (footprint "eagle-import:R0603")
      (fields (field (name "LCSC_PART") "C22975"))
      (libsource (lib "eagle-import") (part "R-US_R0603"))
    )
    (comp (ref "REG5V")
      (value "RED")
      (footprint "eagle-import:CHIPLED_0805")
      (fields (field (name "LCSC_PART") "C72043"))
      (libsource (lib "eagle-import") (part "LEDCHIPLED_0805"))
    )
    (comp (ref "Z3")
      (value "1SMA4753A")
      (footprint "eagle-import:DIOM5226X220N")
      (fields
        (field (name "MANUFACTURER_PART_NUMBER") "1SMA5942BT3G")
        (field (name "MOUSER_PART_NUMBER") "863-1SMA5942BT3G")
        (field (name "LCSC_PART") "C362284")
      )
      (libsource (lib "eagle-import") (part "1SMA5942BT3G"))
    )
  )
  (nets
    (net (code "1") (name "28V") (class "Default")
      (node (ref "F1") (pin "1") (pinfunction "1_1") (pintype "bidirectional"))
      (node (ref "J5") (pin "2") (pinfunction "2_2") (pintype "bidirectional"))
    )
    (net (code "2") (name "28VFUSE") (class "Default")
      (node (ref "C23") (pin "2") (pinfunction "2_2") (pintype "passive"))
      (node (ref "C24") (pin "1") (pinfunction "1_1") (pintype "passive"))
      (node (ref "C3") (pin "1") (pinfunction "+_1") (pintype "bidirectional"))
      (node (ref "C35") (pin "1") (pinfunction "1_1") (pintype "passive"))
      (node (ref "C4") (pin "1") (pinfunction "+_1") (pintype "bidirectional"))
      (node (ref "C5") (pin "1") (pinfunction "+_1") (pintype "bidirectional"))
      (node (ref "C6") (pin "1") (pinfunction "+_1") (pintype "bidirectional"))
      (node (ref "F1") (pin "2") (pinfunction "2_2") (pintype "bidirectional"))
      (node (ref "IC7") (pin "5") (pinfunction "IN_5") (pintype "bidirectional"))
      (node (ref "R26") (pin "1") (pinfunction "1_1") (pintype "passive"))
      (node (ref "T1") (pin "4") (pinfunction "4_4") (pintype "bidirectional"))
      (node (ref "T1") (pin "5") (pinfunction "5_5") (pintype "bidirectional"))
      (node (ref "T1.2") (pin "7") (pinfunction "7_7") (pintype "bidirectional"))
    )
    (net (code "3") (name "AUX1") (class "Default")
      (node (ref "D6") (pin "2") (pinfunction "A_2") (pintype "bidirectional"))
      (node (ref "T1") (pin "16") (pinfunction "16_16") (pintype "bidirectional"))
      (node (ref "T1.2") (pin "2") (pinfunction "2_2") (pintype "bidirectional"))
    )
    (net (code "4") (name "AUXB") (class "Default")
      (node (ref "AUXBUCK_TP") (pin "TP") (pinfunction "TP_TP") (pintype "input"))
      (node (ref "C10") (pin "2") (pinfunction "2_2") (pintype "passive"))
      (node (ref "C12") (pin "1") (pinfunction "1_1") (pintype "passive"))
      (node (ref "C25") (pin "2") (pinfunction "2_2") (pintype "passive"))
      (node (ref "C31") (pin "2") (pinfunction "2_2") (pintype "passive"))
      (node (ref "L2") (pin "1") (pinfunction "1_1") (pintype "bidirectional"))
      (node (ref "PS1") (pin "3") (pinfunction "VIN_3") (pintype "bidirectional"))
      (node (ref "R29") (pin "1") (pinfunction "1_1") (pintype "passive"))
    )
    (net (code "5") (name "AUXD") (class "Default")
      (node (ref "C7") (pin "1") (pinfunction "1_1") (pintype "passive"))
      (node (ref "C9") (pin "1") (pinfunction "1_1") (pintype "passive"))
      (node (ref "IC4") (pin "5") (pinfunction "IN_5") (pintype "bidirectional"))
      (node (ref "R23") (pin "2") (pinfunction "2_2") (pintype "passive"))
      (node (ref "R28") (pin "1") (pinfunction "1_1") (pintype "passive"))
      (node (ref "R31") (pin "2") (pinfunction "2_2") (pintype "passive"))
      (node (ref "Z3") (pin "1") (pinfunction "K_1") (pintype "bidirectional"))
    )
    (net (code "6") (name "BRIDGEGND") (class "Default")
      (node (ref "Q1") (pin "3") (pinfunction "S_3") (pintype "bidirectional"))
      (node (ref "Q2") (pin "3") (pinfunction "S_3") (pintype "bidirectional"))
      (node (ref "R11") (pin "2") (pinfunction "2_2") (pintype "passive"))
      (node (ref "R7") (pin "2") (pinfunction "2_2") (pintype "passive"))
      (node (ref "R8") (pin "2") (pinfunction "2_2") (pintype "passive"))
    )
    (net (code "7") (name "DC+") (class "Default")
      (node (ref "C15") (pin "1") (pinfunction "+_1") (pintype "bidirectional"))
      (node (ref "C16") (pin "1") (pinfunction "+_1") (pintype "bidirectional"))
      (node (ref "C17") (pin "1") (pinfunction "+_1") (pintype "bidirectional"))
      (node (ref "C18") (pin "1") (pinfunction "+_1") (pintype "bidirectional"))
      (node (ref "C19") (pin "2") (pinfunction "2_2") (pintype "bidirectional"))
      (node (ref "HVOUT_TP") (pin "TP") (pinfunction "TP_TP") (pintype "input"))
      (node (ref "J3") (pin "1") (pinfunction "1_1") (pintype "bidirectional"))
      (node (ref "L3") (pin "2") (pinfunction "2_2") (pintype "bidirectional"))
      (node (ref "R19") (pin "2") (pinfunction "2_2") (pintype "passive"))
      (node (ref "R9") (pin "1") (pinfunction "1_1") (pintype "passive"))
    )
    (net (code "8") (name "DRAIN1") (class "Default")
      (node (ref "Q1") (pin "2") (pinfunction "D_2") (pintype "bidirectional"))
      (node (ref "R33") (pin "1") (pinfunction "1_1") (pintype "passive"))
      (node (ref "T1") (pin "7") (pinfunction "7_7") (pintype "bidirectional"))
      (node (ref "T1") (pin "8") (pinfunction "8_8") (pintype "bidirectional"))
      (node (ref "T1.2") (pin "1") (pinfunction "1_1") (pintype "bidirectional"))
      (node (ref "T1.2") (pin "3") (pinfunction "3_3") (pintype "bidirectional"))
    )
    (net (code "9") (name "DRAIN2") (class "Default")
      (node (ref "C36") (pin "2") (pinfunction "2_2") (pintype "passive"))
      (node (ref "Q2") (pin "2") (pinfunction "D_2") (pintype "bidirectional"))
      (node (ref "T1") (pin "1") (pinfunction "1_1") (pintype "bidirectional"))
      (node (ref "T1") (pin "2") (pinfunction "2_2") (pintype "bidirectional"))
      (node (ref "T1.2") (pin "11") (pinfunction "11_11") (pintype "bidirectional"))
      (node (ref "T1.2") (pin "13") (pinfunction "13_13") (pintype "bidirectional"))
    )
    (net (code "10") (name "GNDA") (class "Default")
      (node (ref "C1") (pin "2") (pinfunction "2_2") (pintype "passive"))
      (node (ref "C13") (pin "2") (pinfunction "2_2") (pintype "passive"))
      (node (ref "C14") (pin "2") (pinfunction "2_2") (pintype "passive"))
      (node (ref "C2") (pin "2") (pinfunction "2_2") (pintype "passive"))
      (node (ref "C22") (pin "1") (pinfunction "1_1") (pintype "passive"))
      (node (ref "C23") (pin "1") (pinfunction "1_1") (pintype "passive"))
      (node (ref "C24") (pin "2") (pinfunction "2_2") (pintype "passive"))
      (node (ref "C26") (pin "1") (pinfunction "1_1") (pintype "passive"))
      (node (ref "C28") (pin "1") (pinfunction "1_1") (pintype "passive"))
      (node (ref "C29") (pin "1") (pinfunction "1_1") (pintype "passive"))
      (node (ref "C3") (pin "2") (pinfunction "-_2") (pintype "bidirectional"))
      (node (ref "C32") (pin "1") (pinfunction "1_1") (pintype "passive"))
      (node (ref "C33") (pin "1") (pinfunction "1_1") (pintype "passive"))
      (node (ref "C35") (pin "2") (pinfunction "2_2") (pintype "passive"))
      (node (ref "C4") (pin "2") (pinfunction "-_2") (pintype "bidirectional"))
      (node (ref "C5") (pin "2") (pinfunction "-_2") (pintype "bidirectional"))
      (node (ref "C6") (pin "2") (pinfunction "-_2") (pintype "bidirectional"))
      (node (ref "D5") (pin "2") (pinfunction "A_2") (pintype "bidirectional"))
      (node (ref "IC1") (pin "5") (pinfunction "GND_5") (pintype "bidirectional"))
      (node (ref "IC2") (pin "3") (pinfunction "GND_3") (pintype "bidirectional"))
      (node (ref "IC7") (pin "2") (pinfunction "GND_2") (pintype "bidirectional"))
      (node (ref "J5") (pin "1") (pinfunction "1_1") (pintype "bidirectional"))
      (node (ref "PS2") (pin "1") (pinfunction "-VIN_1") (pintype "bidirectional"))
      (node (ref "Q5") (pin "3") (pinfunction "E_3") (pintype "bidirectional"))
      (node (ref "R12") (pin "2") (pinfunction "2_2") (pintype "passive"))
      (node (ref "R13") (pin "2") (pinfunction "2_2") (pintype "passive"))
      (node (ref "R21") (pin "1") (pinfunction "1_1") (pintype "passive"))
      (node (ref "R24") (pin "1") (pinfunction "1_1") (pintype "passive"))
      (node (ref "R27") (pin "2") (pinfunction "2_2") (pintype "passive"))
      (node (ref "R7") (pin "1") (pinfunction "1_1") (pintype "passive"))
      (node (ref "R8") (pin "1") (pinfunction "1_1") (pintype "passive"))
    )
    (net (code "11") (name "LEDIND") (class "Default")
      (node (ref "R35") (pin "1") (pinfunction "1_1") (pintype "passive"))
      (node (ref "R36") (pin "2") (pinfunction "2_2") (pintype "passive"))
      (node (ref "Z4") (pin "2") (pinfunction "K_2") (pintype "bidirectional"))
    )
    (net (code "12") (name "Net-(13.75V-PadC)") (class "Default")
      (node (ref "13.75V") (pin "C") (pinfunction "C_C") (pintype "passive"))
      (node (ref "R24") (pin "2") (pinfunction "2_2") (pintype "passive"))
    )
    (net (code "13") (name "Net-(C21-Pad2)") (class "Default")
      (node (ref "C21") (pin "2") (pinfunction "2_2") (pintype "passive"))
      (node (ref "R15") (pin "2") (pinfunction "2_2") (pintype "passive"))
    )
    (net (code "14") (name "Net-(C36-Pad1)") (class "Default")
      (node (ref "C36") (pin "1") (pinfunction "1_1") (pintype "passive"))
      (node (ref "R33") (pin "2") (pinfunction "2_2") (pintype "passive"))
    )
    (net (code "15") (name "Net-(D5-K)") (class "Default")
      (node (ref "C27") (pin "1") (pinfunction "1_1") (pintype "passive"))
      (node (ref "D5") (pin "1") (pinfunction "K_1") (pintype "bidirectional"))
      (node (ref "IC7") (pin "6") (pinfunction "SW_6") (pintype "bidirectional"))
      (node (ref "L1") (pin "1") (pinfunction "1_1") (pintype "bidirectional"))
    )
    (net (code "16") (name "Net-(D6-K)") (class "Default")
      (node (ref "D6") (pin "1") (pinfunction "K_1") (pintype "bidirectional"))
      (node (ref "R23") (pin "1") (pinfunction "1_1") (pintype "passive"))
      (node (ref "R31") (pin "1") (pinfunction "1_1") (pintype "passive"))
    )
    (net (code "17") (name "Net-(D7-K)") (class "Default")
      (node (ref "C8") (pin "2") (pinfunction "2_2") (pintype "passive"))
      (node (ref "D7") (pin "1") (pinfunction "K_1") (pintype "bidirectional"))
      (node (ref "IC4") (pin "6") (pinfunction "SW_6") (pintype "bidirectional"))
      (node (ref "L2") (pin "2") (pinfunction "2_2") (pintype "bidirectional"))
    )
    (net (code "18") (name "Net-(D8-K)") (class "Default")
      (node (ref "D8") (pin "1") (pinfunction "K_1") (pintype "bidirectional"))
      (node (ref "D9") (pin "2") (pinfunction "A_2") (pintype "bidirectional"))
    )
    (net (code "19") (name "Net-(D9-K)") (class "Default")
      (node (ref "C33") (pin "2") (pinfunction "2_2") (pintype "passive"))
      (node (ref "D9") (pin "1") (pinfunction "K_1") (pintype "bidirectional"))
      (node (ref "PS2") (pin "3") (pinfunction "_+VIN_3") (pintype "bidirectional"))
    )
    (net (code "20") (name "Net-(HVLED-PadA)") (class "Default")
      (node (ref "HVLED") (pin "A") (pinfunction "A_A") (pintype "passive"))
      (node (ref "R37") (pin "1") (pinfunction "1_1") (pintype "passive"))
    )
    (net (code "21") (name "Net-(HVLED-PadC)") (class "Default")
      (node (ref "HVLED") (pin "C") (pinfunction "C_C") (pintype "passive"))
      (node (ref "T2") (pin "C") (pinfunction "C_C") (pintype "passive"))
    )
    (net (code "22") (name "Net-(IC1-CS)") (class "Default")
      (node (ref "C14") (pin "1") (pinfunction "1_1") (pintype "passive"))
      (node (ref "IC1") (pin "3") (pinfunction "CS_3") (pintype "bidirectional"))
      (node (ref "R11") (pin "1") (pinfunction "1_1") (pintype "passive"))
    )
    (net (code "23") (name "Net-(IC1-ISET)") (class "Default")
      (node (ref "IC1") (pin "2") (pinfunction "ISET_2") (pintype "bidirectional"))
      (node (ref "R12") (pin "1") (pinfunction "1_1") (pintype "passive"))
    )
    (net (code "24") (name "Net-(IC1-OUTA)") (class "Default")
      (node (ref "IC1") (pin "7") (pinfunction "OUTA_7") (pintype "bidirectional"))
      (node (ref "IC2") (pin "2") (pinfunction "INA_2") (pintype "bidirectional"))
    )
    (net (code "25") (name "Net-(IC1-OUTB)") (class "Default")
      (node (ref "IC1") (pin "6") (pinfunction "OUTB_6") (pintype "bidirectional"))
      (node (ref "IC2") (pin "4") (pinfunction "INB_4") (pintype "bidirectional"))
    )
    (net (code "26") (name "Net-(IC1-RT)") (class "Default")
      (node (ref "IC1") (pin "4") (pinfunction "RT_4") (pintype "bidirectional"))
      (node (ref "R13") (pin "1") (pinfunction "1_1") (pintype "passive"))
    )
    (net (code "27") (name "Net-(IC2-ENA)") (class "Default")
      (node (ref "IC2") (pin "1") (pinfunction "ENA_1") (pintype "bidirectional"))
      (node (ref "IC2") (pin "8") (pinfunction "ENB_8") (pintype "bidirectional"))
      (node (ref "R2") (pin "1") (pinfunction "1_1") (pintype "passive"))
    )
    (net (code "28") (name "Net-(IC2-OUT1)") (class "Default")
      (node (ref "IC2") (pin "7") (pinfunction "OUT1_7") (pintype "bidirectional"))
      (node (ref "R3") (pin "1") (pinfunction "1_1") (pintype "passive"))
      (node (ref "R4") (pin "1") (pinfunction "1_1") (pintype "passive"))
    )
    (net (code "29") (name "Net-(IC2-OUT2)") (class "Default")
      (node (ref "IC2") (pin "5") (pinfunction "OUT2_5") (pintype "bidirectional"))
      (node (ref "R5") (pin "1") (pinfunction "1_1") (pintype "passive"))
      (node (ref "R6") (pin "1") (pinfunction "1_1") (pintype "passive"))
    )
    (net (code "30") (name "Net-(IC3-ADJ)") (class "Default")
      (node (ref "IC3") (pin "1") (pinfunction "ADJ_1") (pintype "input"))
      (node (ref "R20") (pin "1") (pinfunction "1_1") (pintype "passive"))
      (node (ref "R21") (pin "2") (pinfunction "2_2") (pintype "passive"))
    )
    (net (code "31") (name "Net-(IC4-BS)") (class "Default")
      (node (ref "C8") (pin "1") (pinfunction "1_1") (pintype "passive"))
      (node (ref "IC4") (pin "1") (pinfunction "BS_1") (pintype "bidirectional"))
    )
    (net (code "32") (name "Net-(IC4-EN)") (class "Default")
      (node (ref "IC4") (pin "4") (pinfunction "EN_4") (pintype "bidirectional"))
      (node (ref "R28") (pin "2") (pinfunction "2_2") (pintype "passive"))
    )
    (net (code "33") (name "Net-(IC4-FB)") (class "Default")
      (node (ref "C12") (pin "2") (pinfunction "2_2") (pintype "passive"))
      (node (ref "IC4") (pin "3") (pinfunction "FB_3") (pintype "bidirectional"))
      (node (ref "R29") (pin "2") (pinfunction "2_2") (pintype "passive"))
      (node (ref "R30") (pin "1") (pinfunction "1_1") (pintype "passive"))
    )
    (net (code "34") (name "Net-(IC6-CATHODE)") (class "Default")
      (node (ref "C20") (pin "2") (pinfunction "2_2") (pintype "passive"))
      (node (ref "IC6") (pin "1") (pinfunction "CATHODE_1") (pintype "bidirectional"))
      (node (ref "Q5") (pin "2") (pinfunction "K_2") (pintype "bidirectional"))
      (node (ref "R15") (pin "1") (pinfunction "1_1") (pintype "passive"))
    )
    (net (code "35") (name "Net-(IC6-REF)") (class "Default")
      (node (ref "C20") (pin "1") (pinfunction "1_1") (pintype "passive"))
      (node (ref "C21") (pin "1") (pinfunction "1_1") (pintype "passive"))
      (node (ref "IC6") (pin "2") (pinfunction "REF_2") (pintype "bidirectional"))
      (node (ref "J1") (pin "1") (pinfunction "1_1") (pintype "passive"))
      (node (ref "R14") (pin "2") (pinfunction "2_2") (pintype "passive"))
      (node (ref "R16") (pin "2") (pinfunction "2_2") (pintype "passive"))
    )
    (net (code "36") (name "Net-(IC7-BS)") (class "Default")
      (node (ref "C27") (pin "2") (pinfunction "2_2") (pintype "passive"))
      (node (ref "IC7") (pin "1") (pinfunction "BS_1") (pintype "bidirectional"))
    )
    (net (code "37") (name "Net-(IC7-EN)") (class "Default")
      (node (ref "IC7") (pin "4") (pinfunction "EN_4") (pintype "bidirectional"))
      (node (ref "R26") (pin "2") (pinfunction "2_2") (pintype "passive"))
    )
    (net (code "38") (name "Net-(IC7-FB)") (class "Default")
      (node (ref "C30") (pin "2") (pinfunction "2_2") (pintype "passive"))
      (node (ref "IC7") (pin "3") (pinfunction "FB_3") (pintype "bidirectional"))
      (node (ref "R25") (pin "1") (pinfunction "1_1") (pintype "passive"))
      (node (ref "R27") (pin "1") (pinfunction "1_1") (pintype "passive"))
    )
    (net (code "39") (name "Net-(Q1-G)") (class "Default")
      (node (ref "GATE1_TP") (pin "TP") (pinfunction "TP_TP") (pintype "input"))
      (node (ref "Q1") (pin "1") (pinfunction "G_1") (pintype "bidirectional"))
      (node (ref "R3") (pin "2") (pinfunction "2_2") (pintype "passive"))
      (node (ref "R4") (pin "2") (pinfunction "2_2") (pintype "passive"))
    )
    (net (code "40") (name "Net-(Q2-G)") (class "Default")
      (node (ref "GATE2_TP") (pin "TP") (pinfunction "TP_TP") (pintype "input"))
      (node (ref "Q2") (pin "1") (pinfunction "G_1") (pintype "bidirectional"))
      (node (ref "R5") (pin "2") (pinfunction "2_2") (pintype "passive"))
      (node (ref "R6") (pin "2") (pinfunction "2_2") (pintype "passive"))
    )
    (net (code "41") (name "Net-(Q5-A)") (class "Default")
      (node (ref "Q5") (pin "1") (pinfunction "A_1") (pintype "bidirectional"))
      (node (ref "R17") (pin "2") (pinfunction "2_2") (pintype "passive"))
    )
    (net (code "42") (name "Net-(R10-Pad1)") (class "Default")
      (node (ref "R10") (pin "1") (pinfunction "1_1") (pintype "passive"))
      (node (ref "R9") (pin "2") (pinfunction "2_2") (pintype "passive"))
    )
    (net (code "43") (name "Net-(R10-Pad2)") (class "Default")
      (node (ref "R10") (pin "2") (pinfunction "2_2") (pintype "passive"))
      (node (ref "R14") (pin "1") (pinfunction "1_1") (pintype "passive"))
    )
    (net (code "44") (name "Net-(R16-Pad1)") (class "Default")
      (node (ref "R16") (pin "1") (pinfunction "1_1") (pintype "passive"))
      (node (ref "R18") (pin "2") (pinfunction "2_2") (pintype "passive"))
    )
    (net (code "45") (name "Net-(R19-Pad1)") (class "Default")
      (node (ref "R19") (pin "1") (pinfunction "1_1") (pintype "passive"))
      (node (ref "R34") (pin "2") (pinfunction "2_2") (pintype "passive"))
    )
    (net (code "46") (name "Net-(R32-Pad2)") (class "Default")
      (node (ref "R32") (pin "2") (pinfunction "2_2") (pintype "passive"))
      (node (ref "REG5V") (pin "C") (pinfunction "C_C") (pintype "passive"))
    )
    (net (code "47") (name "Net-(R34-Pad1)") (class "Default")
      (node (ref "R34") (pin "1") (pinfunction "1_1") (pintype "passive"))
      (node (ref "R35") (pin "2") (pinfunction "2_2") (pintype "passive"))
    )
    (net (code "48") (name "Net-(SJ1-Pad1)") (class "Default")
      (node (ref "SJ1") (pin "1") (pinfunction "1_1") (pintype "passive"))
      (node (ref "T1") (pin "11") (pinfunction "11_11") (pintype "bidirectional"))
    )
    (net (code "49") (name "Net-(SJ1-Pad3)") (class "Default")
      (node (ref "SJ1") (pin "3") (pinfunction "3_3") (pintype "passive"))
      (node (ref "T1") (pin "13") (pinfunction "13_13") (pintype "bidirectional"))
    )
    (net (code "50") (name "Net-(Z4-A)") (class "Default")
      (node (ref "T2") (pin "B") (pinfunction "B_B") (pintype "passive"))
      (node (ref "Z4") (pin "1") (pinfunction "A_1") (pintype "bidirectional"))
    )
    (net (code "51") (name "OPTO-EMITT") (class "Default")
      (node (ref "IC1") (pin "1") (pinfunction "CTRL_1") (pintype "bidirectional"))
      (node (ref "Q5") (pin "4") (pinfunction "C_4") (pintype "bidirectional"))
      (node (ref "R1") (pin "2") (pinfunction "2_2") (pintype "passive"))
    )
    (net (code "52") (name "PRE") (class "Default")
      (node (ref "C26") (pin "2") (pinfunction "2_2") (pintype "passive"))
      (node (ref "C28") (pin "2") (pinfunction "2_2") (pintype "passive"))
      (node (ref "C29") (pin "2") (pinfunction "2_2") (pintype "passive"))
      (node (ref "C30") (pin "1") (pinfunction "1_1") (pintype "passive"))
      (node (ref "IC3") (pin "3") (pinfunction "IN_3") (pintype "input"))
      (node (ref "L1") (pin "2") (pinfunction "2_2") (pintype "bidirectional"))
      (node (ref "MAINBUCK_TP") (pin "TP") (pinfunction "TP_TP") (pintype "input"))
      (node (ref "R25") (pin "2") (pinfunction "2_2") (pintype "passive"))
    )
    (net (code "53") (name "PWRGND") (class "Default")
      (node (ref "C10") (pin "1") (pinfunction "1_1") (pintype "passive"))
      (node (ref "C11") (pin "1") (pinfunction "1_1") (pintype "passive"))
      (node (ref "C15") (pin "2") (pinfunction "-_2") (pintype "bidirectional"))
      (node (ref "C16") (pin "2") (pinfunction "-_2") (pintype "bidirectional"))
      (node (ref "C17") (pin "2") (pinfunction "-_2") (pintype "bidirectional"))
      (node (ref "C18") (pin "2") (pinfunction "-_2") (pintype "bidirectional"))
      (node (ref "C19") (pin "1") (pinfunction "1_1") (pintype "bidirectional"))
      (node (ref "C25") (pin "1") (pinfunction "1_1") (pintype "passive"))
      (node (ref "C31") (pin "1") (pinfunction "1_1") (pintype "passive"))
      (node (ref "C34") (pin "1") (pinfunction "1_1") (pintype "passive"))
      (node (ref "C7") (pin "2") (pinfunction "2_2") (pintype "passive"))
      (node (ref "C9") (pin "2") (pinfunction "2_2") (pintype "passive"))
      (node (ref "D1") (pin "1") (pinfunction "A1_1") (pintype "bidirectional"))
      (node (ref "D1") (pin "3") (pinfunction "A2_3") (pintype "bidirectional"))
      (node (ref "D4") (pin "1") (pinfunction "A1_1") (pintype "bidirectional"))
      (node (ref "D4") (pin "3") (pinfunction "A2_3") (pintype "bidirectional"))
      (node (ref "D7") (pin "2") (pinfunction "A_2") (pintype "bidirectional"))
      (node (ref "IC4") (pin "2") (pinfunction "GND_2") (pintype "bidirectional"))
      (node (ref "IC6") (pin "3") (pinfunction "ANODE_3") (pintype "bidirectional"))
      (node (ref "J1") (pin "2") (pinfunction "2_2") (pintype "passive"))
      (node (ref "J3") (pin "2") (pinfunction "2_2") (pintype "bidirectional"))
      (node (ref "PS1") (pin "1") (pinfunction "GND_1") (pintype "bidirectional"))
      (node (ref "PS2") (pin "7") (pinfunction "-VOUT_7") (pintype "bidirectional"))
      (node (ref "PWRGND_TP") (pin "TP") (pinfunction "TP_TP") (pintype "input"))
      (node (ref "R18") (pin "1") (pinfunction "1_1") (pintype "passive"))
      (node (ref "R30") (pin "2") (pinfunction "2_2") (pintype "passive"))
      (node (ref "R32") (pin "1") (pinfunction "1_1") (pintype "passive"))
      (node (ref "R36") (pin "1") (pinfunction "1_1") (pintype "passive"))
      (node (ref "T1") (pin "15") (pinfunction "15_15") (pintype "bidirectional"))
      (node (ref "T1.2") (pin "4") (pinfunction "4_4") (pintype "bidirectional"))
      (node (ref "T2") (pin "E") (pinfunction "E_E") (pintype "passive"))
      (node (ref "Z3") (pin "2") (pinfunction "A_2") (pintype "bidirectional"))
    )
    (net (code "54") (name "RECT") (class "Default")
      (node (ref "D2") (pin "2") (pinfunction "K_2") (pintype "bidirectional"))
      (node (ref "D3") (pin "2") (pinfunction "K_2") (pintype "bidirectional"))
      (node (ref "L3") (pin "1") (pinfunction "1_1") (pintype "bidirectional"))
    )
    (net (code "55") (name "REG") (class "Default")
      (node (ref "13.75V") (pin "A") (pinfunction "A_A") (pintype "passive"))
      (node (ref "13.75V_TP") (pin "TP") (pinfunction "TP_TP") (pintype "input"))
      (node (ref "C1") (pin "1") (pinfunction "1_1") (pintype "passive"))
      (node (ref "C13") (pin "1") (pinfunction "1_1") (pintype "passive"))
      (node (ref "C2") (pin "1") (pinfunction "1_1") (pintype "passive"))
      (node (ref "C22") (pin "2") (pinfunction "2_2") (pintype "passive"))
      (node (ref "C32") (pin "2") (pinfunction "2_2") (pintype "passive"))
      (node (ref "D8") (pin "2") (pinfunction "A_2") (pintype "bidirectional"))
      (node (ref "IC1") (pin "8") (pinfunction "VDD_8") (pintype "bidirectional"))
      (node (ref "IC2") (pin "6") (pinfunction "VDD_6") (pintype "bidirectional"))
      (node (ref "IC3") (pin "4") (pinfunction "OUT_4") (pintype "passive"))
      (node (ref "R1") (pin "1") (pinfunction "1_1") (pintype "passive"))
      (node (ref "R2") (pin "2") (pinfunction "2_2") (pintype "passive"))
      (node (ref "R20") (pin "2") (pinfunction "2_2") (pintype "passive"))
    )
    (net (code "56") (name "REG5V") (class "Default")
      (node (ref "AUX5V_TP") (pin "TP") (pinfunction "TP_TP") (pintype "input"))
      (node (ref "C11") (pin "2") (pinfunction "2_2") (pintype "passive"))
      (node (ref "C34") (pin "2") (pinfunction "2_2") (pintype "passive"))
      (node (ref "PS1") (pin "2") (pinfunction "VOUT_2") (pintype "bidirectional"))
      (node (ref "PS2") (pin "8") (pinfunction "+VOUT_8") (pintype "bidirectional"))
      (node (ref "R17") (pin "1") (pinfunction "1_1") (pintype "passive"))
      (node (ref "R37") (pin "2") (pinfunction "2_2") (pintype "passive"))
      (node (ref "REG5V") (pin "A") (pinfunction "A_A") (pintype "passive"))
    )
    (net (code "57") (name "TRANS1") (class "Default")
      (node (ref "D3") (pin "1") (pinfunction "A1_1") (pintype "bidirectional"))
      (node (ref "D3") (pin "3") (pinfunction "A2_3") (pintype "bidirectional"))
      (node (ref "D4") (pin "2") (pinfunction "K_2") (pintype "bidirectional"))
      (node (ref "SJ1") (pin "2") (pinfunction "2_2") (pintype "passive"))
      (node (ref "T1.2") (pin "8") (pinfunction "8_8") (pintype "bidirectional"))
    )
    (net (code "58") (name "TRANS2") (class "Default")
      (node (ref "D1") (pin "2") (pinfunction "K_2") (pintype "bidirectional"))
      (node (ref "D2") (pin "1") (pinfunction "A1_1") (pintype "bidirectional"))
      (node (ref "D2") (pin "3") (pinfunction "A2_3") (pintype "bidirectional"))
      (node (ref "T1") (pin "9") (pinfunction "9_9") (pintype "bidirectional"))
      (node (ref "T1.2") (pin "14") (pinfunction "14_14") (pintype "bidirectional"))
    )
    (net (code "59") (name "unconnected-(PS2-NA-Pad14)") (class "Default")
      (node (ref "PS2") (pin "14") (pinfunction "NA_14") (pintype "bidirectional"))
    )
    (net (code "60") (name "unconnected-(T1-Pad3)") (class "Default")
      (node (ref "T1") (pin "3") (pinfunction "3_3") (pintype "bidirectional"))
    )
    (net (code "61") (name "unconnected-(T1-Pad6)") (class "Default")
      (node (ref "T1") (pin "6") (pinfunction "6_6") (pintype "bidirectional"))
    )
    (net (code "62") (name "unconnected-(T1-Pad10)") (class "Default")
      (node (ref "T1") (pin "10") (pinfunction "10_10") (pintype "bidirectional"))
    )
    (net (code "63") (name "unconnected-(T1-Pad12)") (class "Default")
      (node (ref "T1") (pin "12") (pinfunction "12_12") (pintype "bidirectional"))
    )
    (net (code "64") (name "unconnected-(T1-Pad14)") (class "Default")
      (node (ref "T1") (pin "14") (pinfunction "14_14") (pintype "bidirectional"))
    )
    (net (code "65") (name "unconnected-(T1.2-Pad5)") (class "Default")
      (node (ref "T1.2") (pin "5") (pinfunction "5_5") (pintype "bidirectional"))
    )
    (net (code "66") (name "unconnected-(T1.2-Pad6)") (class "Default")
      (node (ref "T1.2") (pin "6") (pinfunction "6_6") (pintype "bidirectional"))
    )
    (net (code "67") (name "unconnected-(T1.2-Pad9)") (class "Default")
      (node (ref "T1.2") (pin "9") (pinfunction "9_9") (pintype "bidirectional"))
    )
    (net (code "68") (name "unconnected-(T1.2-Pad10)") (class "Default")
      (node (ref "T1.2") (pin "10") (pinfunction "10_10") (pintype "bidirectional"))
    )
    (net (code "69") (name "unconnected-(T1.2-Pad12)") (class "Default")
      (node (ref "T1.2") (pin "12") (pinfunction "12_12") (pintype "bidirectional"))
    )
  )
)
